# QCopterMV_POWER_Sch.net
KiCad netlist of a schematic drawn in Altium Designer
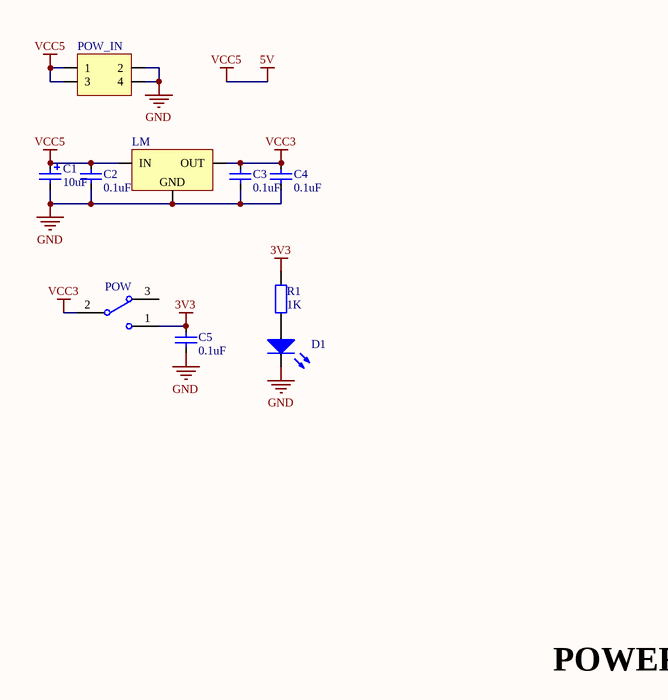
[diagram p0: QCopterMV_POWER_Sch.SchDoc]

(export (version "E")
  (design (tool "Eeschema 10.0.6"))
  (components
    (comp (ref "C1")
      (value "10uF")
      (footprint "PCB_Passive:CAP_TAN_B1210")
      (description "Capacitor")
      (fields (field (name "Comment") "Cap_Tan_1210"))
      (libsource (lib "SCH_Passive") (part "Cap_Tan_1210"))
    )
    (comp (ref "C2")
      (value "0.1uF")
      (footprint "PCB_Passive:CAP_0603")
      (description "Capacitor")
      (fields (field (name "Comment") "Cap_0603"))
      (libsource (lib "SCH_Passive") (part "Cap_0603"))
    )
    (comp (ref "C3")
      (value "0.1uF")
      (footprint "PCB_Passive:CAP_0603")
      (description "Capacitor")
      (fields (field (name "Comment") "Cap_0603"))
      (libsource (lib "SCH_Passive") (part "Cap_0603"))
    )
    (comp (ref "C4")
      (value "0.1uF")
      (footprint "PCB_Passive:CAP_0603")
      (description "Capacitor")
      (fields (field (name "Comment") "Cap_0603"))
      (libsource (lib "SCH_Passive") (part "Cap_0603"))
    )
    (comp (ref "C5")
      (value "0.1uF")
      (footprint "PCB_Passive:CAP_0603")
      (description "Capacitor")
      (fields (field (name "Comment") "Cap_0603"))
      (libsource (lib "SCH_Passive") (part "Cap_0603"))
    )
    (comp (ref "D1")
      (value "LED_0603_BLUE")
      (footprint "PCB_Active:LED_0603_BLUE")
      (description "LED")
      (libsource (lib "SCH_Active") (part "LED_0603_BLUE"))
    )
    (comp (ref "LM")
      (value "LM1117")
      (footprint "PCB_IC:SOT223")
      (description "Power")
      (libsource (lib "SCH_IC") (part "LM1117"))
    )
    (comp (ref "POW")
      (value "SW-SPDT")
      (footprint "PCB_Switch:SW_T")
      (description "SPDT Subminiature Toggle Switch, Right Angle Mounting, Vertical Actuation")
      (fields (field (name "PUBLISHER") "Altium Limited"))
      (libsource (lib "SCH_Switch") (part "SW-SPDT_1"))
    )
    (comp (ref "POW_IN")
      (value "HDR2X2_90_2.54")
      (footprint "PCB_Connector:HDR2X2_90_2.54")
      (description "Header")
      (libsource (lib "SCH_Connector") (part "HDR2X2_90_2.54"))
    )
    (comp (ref "R1")
      (value "1K")
      (footprint "PCB_Passive:RES_0603")
      (description "Resistor")
      (fields (field (name "Comment") "Res_0603"))
      (libsource (lib "SCH_Passive") (part "Res_0603"))
    )
  )
  (nets
    (net (code "1") (name "3V3") (class "Default")
      (node (ref "C5") (pin "2") (pinfunction "2_2") (pintype "passive"))
      (node (ref "POW") (pin "1") (pinfunction "1_1") (pintype "passive"))
      (node (ref "R1") (pin "2") (pinfunction "2_2") (pintype "passive"))
    )
    (net (code "2") (name "5V") (class "Default")
      (node (ref "C1") (pin "1") (pinfunction "1_1") (pintype "passive"))
      (node (ref "C2") (pin "2") (pinfunction "2_2") (pintype "passive"))
      (node (ref "LM") (pin "3") (pinfunction "IN_3") (pintype "power_in"))
      (node (ref "POW_IN") (pin "1") (pinfunction "1_1") (pintype "passive"))
      (node (ref "POW_IN") (pin "3") (pinfunction "3_3") (pintype "passive"))
    )
    (net (code "3") (name "GND") (class "Default")
      (node (ref "C1") (pin "2") (pinfunction "2_2") (pintype "passive"))
      (node (ref "C2") (pin "1") (pinfunction "1_1") (pintype "passive"))
      (node (ref "C3") (pin "1") (pinfunction "1_1") (pintype "passive"))
      (node (ref "C4") (pin "1") (pinfunction "1_1") (pintype "passive"))
      (node (ref "C5") (pin "1") (pinfunction "1_1") (pintype "passive"))
      (node (ref "D1") (pin "2") (pinfunction "K_2") (pintype "passive"))
      (node (ref "LM") (pin "1") (pinfunction "GND_1") (pintype "power_in"))
      (node (ref "POW_IN") (pin "2") (pinfunction "2_2") (pintype "passive"))
      (node (ref "POW_IN") (pin "4") (pinfunction "4_4") (pintype "passive"))
    )
    (net (code "4") (name "Net-(D1-A)") (class "Default")
      (node (ref "D1") (pin "1") (pinfunction "A_1") (pintype "passive"))
      (node (ref "R1") (pin "1") (pinfunction "1_1") (pintype "passive"))
    )
    (net (code "5") (name "VCC3") (class "Default")
      (node (ref "C3") (pin "2") (pinfunction "2_2") (pintype "passive"))
      (node (ref "C4") (pin "2") (pinfunction "2_2") (pintype "passive"))
      (node (ref "LM") (pin "2") (pinfunction "OUT_2") (pintype "power_in"))
      (node (ref "POW") (pin "2") (pinfunction "2_2") (pintype "passive"))
    )
    (net (code "6") (name "unconnected-(POW-Pad3)") (class "Default")
      (node (ref "POW") (pin "3") (pinfunction "3_3") (pintype "passive"))
    )
  )
)
